# power.net
KiCad netlist of a schematic drawn in Altium Designer
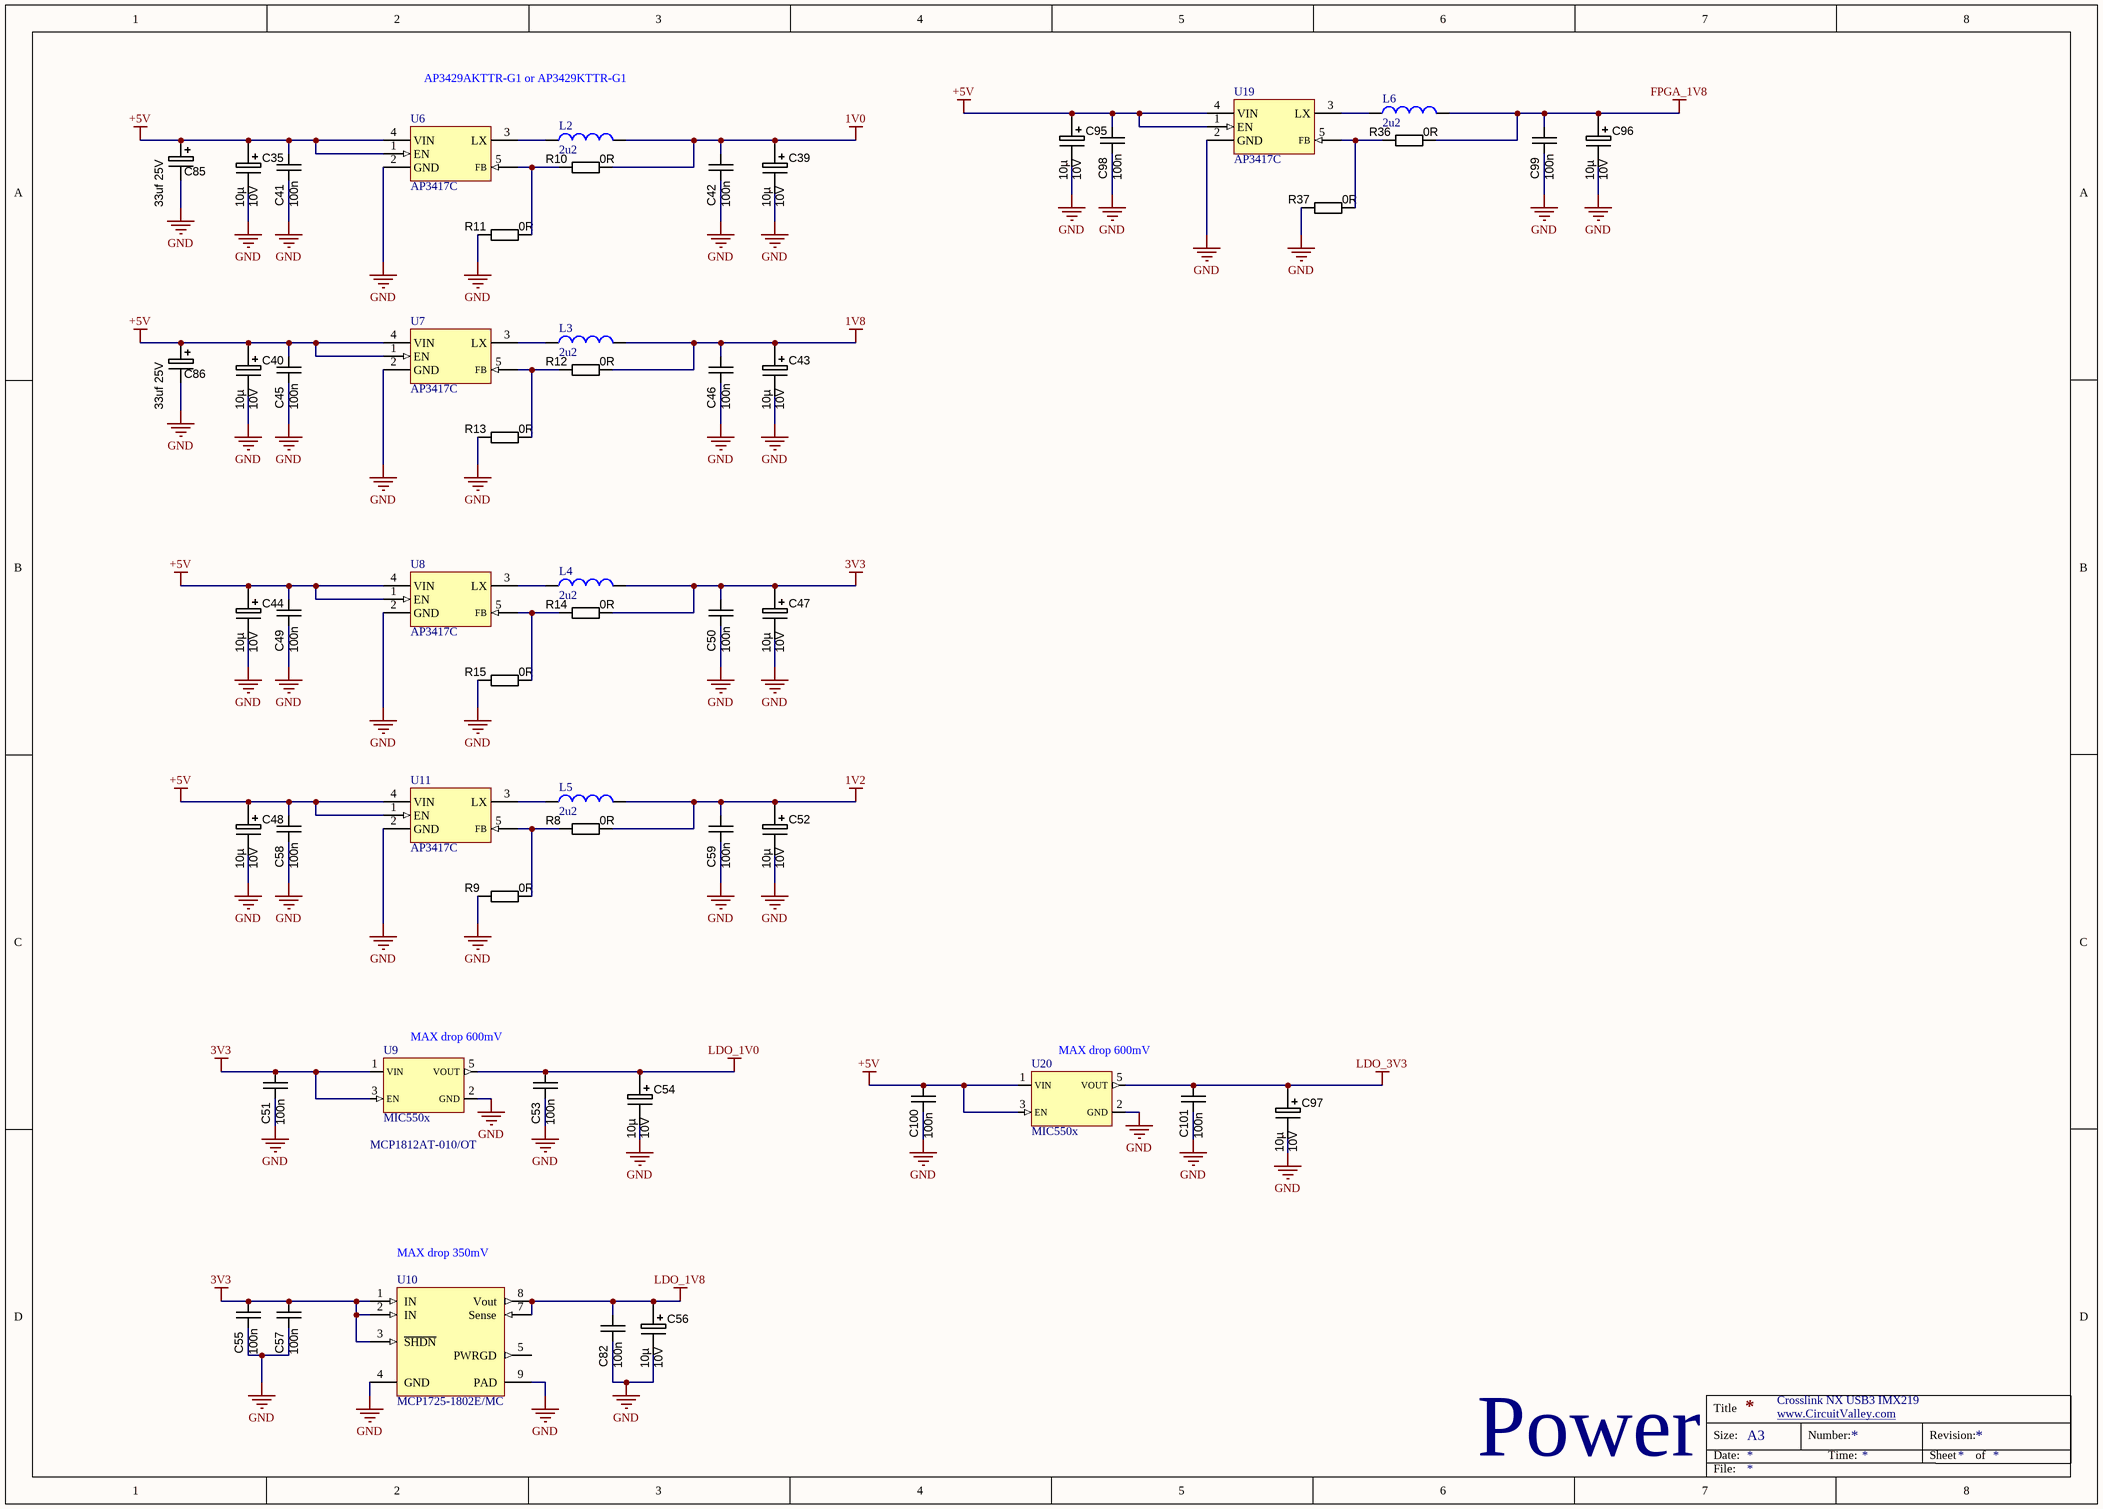
[diagram p0: power.SchDoc]

(export (version "E")
  (design (tool "Eeschema 10.0.6"))
  (components
    (comp (ref "C35")
      (value "10µ")
      (footprint "CAPMP3528X210N")
      (description "Capacitor SMD Tantalum 47uF 20% 6.3V 1210")
      (fields (field (name "TOLERANCE") "±20%") (field (name "RATINGS") "10V"))
      (libsource (lib "PBL - Capacitors") (part "CAPT_47u_1210_6V3"))
    )
    (comp (ref "C39")
      (value "10µ")
      (footprint "CAPMP3528X210N")
      (description "Capacitor SMD Tantalum 47uF 20% 6.3V 1210")
      (fields (field (name "TOLERANCE") "±20%") (field (name "RATINGS") "10V"))
      (libsource (lib "PBL - Capacitors") (part "CAPT_47u_1210_6V3"))
    )
    (comp (ref "C40")
      (value "10µ")
      (footprint "CAPMP3528X210N")
      (description "Capacitor SMD Tantalum 47uF 20% 6.3V 1210")
      (fields (field (name "TOLERANCE") "±20%") (field (name "RATINGS") "10V"))
      (libsource (lib "PBL - Capacitors") (part "CAPT_47u_1210_6V3"))
    )
    (comp (ref "C41")
      (value "100n")
      (footprint "CAPC1608N")
      (description "Capacitor SMD Cer 10pF 5% 50V NP0 0603")
      (fields (field (name "TOLERANCE") "±5%") (field (name "PART") "C0603X104K5RAC"))
      (libsource (lib "PBL - Capacitors") (part "CAPC_10p_0603_NP0_1%_50V"))
    )
    (comp (ref "C42")
      (value "100n")
      (footprint "CAPC1608N")
      (description "Capacitor SMD Cer 10pF 5% 50V NP0 0603")
      (fields (field (name "TOLERANCE") "±5%") (field (name "PART") "C0603X104K5RAC"))
      (libsource (lib "PBL - Capacitors") (part "CAPC_10p_0603_NP0_1%_50V"))
    )
    (comp (ref "C43")
      (value "10µ")
      (footprint "CAPMP3528X210N")
      (description "Capacitor SMD Tantalum 47uF 20% 6.3V 1210")
      (fields (field (name "TOLERANCE") "±20%") (field (name "RATINGS") "10V"))
      (libsource (lib "PBL - Capacitors") (part "CAPT_47u_1210_6V3"))
    )
    (comp (ref "C44")
      (value "10µ")
      (footprint "CAPMP3528X210N")
      (description "Capacitor SMD Tantalum 47uF 20% 6.3V 1210")
      (fields (field (name "TOLERANCE") "±20%") (field (name "RATINGS") "10V"))
      (libsource (lib "PBL - Capacitors") (part "CAPT_47u_1210_6V3"))
    )
    (comp (ref "C45")
      (value "100n")
      (footprint "CAPC1608N")
      (description "Capacitor SMD Cer 10pF 5% 50V NP0 0603")
      (fields (field (name "TOLERANCE") "±5%") (field (name "PART") "C0603X104K5RAC"))
      (libsource (lib "PBL - Capacitors") (part "CAPC_10p_0603_NP0_1%_50V"))
    )
    (comp (ref "C46")
      (value "100n")
      (footprint "CAPC1608N")
      (description "Capacitor SMD Cer 10pF 5% 50V NP0 0603")
      (fields (field (name "TOLERANCE") "±5%") (field (name "PART") "C0603X104K5RAC"))
      (libsource (lib "PBL - Capacitors") (part "CAPC_10p_0603_NP0_1%_50V"))
    )
    (comp (ref "C47")
      (value "10µ")
      (footprint "CAPMP3528X210N")
      (description "Capacitor SMD Tantalum 47uF 20% 6.3V 1210")
      (fields (field (name "TOLERANCE") "±20%") (field (name "RATINGS") "10V"))
      (libsource (lib "PBL - Capacitors") (part "CAPT_47u_1210_6V3"))
    )
    (comp (ref "C48")
      (value "10µ")
      (footprint "CAPMP3528X210N")
      (description "Capacitor SMD Tantalum 47uF 20% 6.3V 1210")
      (fields (field (name "TOLERANCE") "±20%") (field (name "RATINGS") "10V"))
      (libsource (lib "PBL - Capacitors") (part "CAPT_47u_1210_6V3"))
    )
    (comp (ref "C49")
      (value "100n")
      (footprint "CAPC1608N")
      (description "Capacitor SMD Cer 10pF 5% 50V NP0 0603")
      (fields (field (name "TOLERANCE") "±5%") (field (name "PART") "C0603X104K5RAC"))
      (libsource (lib "PBL - Capacitors") (part "CAPC_10p_0603_NP0_1%_50V"))
    )
    (comp (ref "C50")
      (value "100n")
      (footprint "CAPC1608N")
      (description "Capacitor SMD Cer 10pF 5% 50V NP0 0603")
      (fields (field (name "TOLERANCE") "±5%") (field (name "PART") "C0603X104K5RAC"))
      (libsource (lib "PBL - Capacitors") (part "CAPC_10p_0603_NP0_1%_50V"))
    )
    (comp (ref "C51")
      (value "100n")
      (footprint "CAPC1608N")
      (description "Capacitor SMD Cer 10pF 5% 50V NP0 0603")
      (fields (field (name "TOLERANCE") "±5%") (field (name "PART") "C0603X104K5RAC"))
      (libsource (lib "PBL - Capacitors") (part "CAPC_10p_0603_NP0_1%_50V"))
    )
    (comp (ref "C52")
      (value "10µ")
      (footprint "CAPMP3528X210N")
      (description "Capacitor SMD Tantalum 47uF 20% 6.3V 1210")
      (fields (field (name "TOLERANCE") "±20%") (field (name "RATINGS") "10V"))
      (libsource (lib "PBL - Capacitors") (part "CAPT_47u_1210_6V3"))
    )
    (comp (ref "C53")
      (value "100n")
      (footprint "CAPC1608N")
      (description "Capacitor SMD Cer 10pF 5% 50V NP0 0603")
      (fields (field (name "TOLERANCE") "±5%") (field (name "PART") "C0603X104K5RAC"))
      (libsource (lib "PBL - Capacitors") (part "CAPC_10p_0603_NP0_1%_50V"))
    )
    (comp (ref "C54")
      (value "10µ")
      (footprint "CAPMP3528X210N")
      (description "Capacitor SMD Tantalum 47uF 20% 6.3V 1210")
      (fields (field (name "TOLERANCE") "±20%") (field (name "RATINGS") "10V"))
      (libsource (lib "PBL - Capacitors") (part "CAPT_47u_1210_6V3"))
    )
    (comp (ref "C55")
      (value "100n")
      (footprint "CAPC1608N")
      (description "Capacitor SMD Cer 10pF 5% 50V NP0 0603")
      (fields (field (name "TOLERANCE") "±5%") (field (name "PART") "C0603X104K5RAC"))
      (libsource (lib "PBL - Capacitors") (part "CAPC_10p_0603_NP0_1%_50V"))
    )
    (comp (ref "C56")
      (value "10µ")
      (footprint "CAPMP3528X210N")
      (description "Capacitor SMD Tantalum 47uF 20% 6.3V 1210")
      (fields (field (name "TOLERANCE") "±20%") (field (name "RATINGS") "10V"))
      (libsource (lib "PBL - Capacitors") (part "CAPT_47u_1210_6V3"))
    )
    (comp (ref "C57")
      (value "100n")
      (footprint "CAPC1608N")
      (description "Capacitor SMD Cer 10pF 5% 50V NP0 0603")
      (fields (field (name "TOLERANCE") "±5%") (field (name "PART") "C0603X104K5RAC"))
      (libsource (lib "PBL - Capacitors") (part "CAPC_10p_0603_NP0_1%_50V"))
    )
    (comp (ref "C58")
      (value "100n")
      (footprint "CAPC1608N")
      (description "Capacitor SMD Cer 10pF 5% 50V NP0 0603")
      (fields (field (name "TOLERANCE") "±5%") (field (name "PART") "C0603X104K5RAC"))
      (libsource (lib "PBL - Capacitors") (part "CAPC_10p_0603_NP0_1%_50V"))
    )
    (comp (ref "C59")
      (value "100n")
      (footprint "CAPC1608N")
      (description "Capacitor SMD Cer 10pF 5% 50V NP0 0603")
      (fields (field (name "TOLERANCE") "±5%") (field (name "PART") "C0603X104K5RAC"))
      (libsource (lib "PBL - Capacitors") (part "CAPC_10p_0603_NP0_1%_50V"))
    )
    (comp (ref "C82")
      (value "100n")
      (footprint "CAPC1608N")
      (description "Capacitor SMD Cer 10pF 5% 50V NP0 0603")
      (fields (field (name "TOLERANCE") "±5%") (field (name "PART") "C0603X104K5RAC"))
      (libsource (lib "PBL - Capacitors") (part "CAPC_10p_0603_NP0_1%_50V"))
    )
    (comp (ref "C85")
      (value "33uf 25V")
      (footprint "CAPMP7343X310N")
      (description "Capacitor SMD Tant 330uF 20% 6V3 2917")
      (fields
        (field (name "TOLERANCE") "±20%")
        (field (name "MANUFACTURER PART NUMBER") "T520D337M006ATE015")
      )
      (libsource (lib "PBL - Capacitors") (part "CAPT_330u_2917_6V3"))
    )
    (comp (ref "C86")
      (value "33uf 25V")
      (footprint "CAPMP7343X310N")
      (description "Capacitor SMD Tant 330uF 20% 6V3 2917")
      (fields
        (field (name "TOLERANCE") "±20%")
        (field (name "MANUFACTURER PART NUMBER") "T520D337M006ATE015")
      )
      (libsource (lib "PBL - Capacitors") (part "CAPT_330u_2917_6V3"))
    )
    (comp (ref "C95")
      (value "10µ")
      (footprint "CAPMP3528X210N")
      (description "Capacitor SMD Tantalum 47uF 20% 6.3V 1210")
      (fields (field (name "TOLERANCE") "±20%") (field (name "RATINGS") "10V"))
      (libsource (lib "PBL - Capacitors") (part "CAPT_47u_1210_6V3"))
    )
    (comp (ref "C96")
      (value "10µ")
      (footprint "CAPMP3528X210N")
      (description "Capacitor SMD Tantalum 47uF 20% 6.3V 1210")
      (fields (field (name "TOLERANCE") "±20%") (field (name "RATINGS") "10V"))
      (libsource (lib "PBL - Capacitors") (part "CAPT_47u_1210_6V3"))
    )
    (comp (ref "C97")
      (value "10µ")
      (footprint "CAPMP3528X210N")
      (description "Capacitor SMD Tantalum 47uF 20% 6.3V 1210")
      (fields (field (name "TOLERANCE") "±20%") (field (name "RATINGS") "10V"))
      (libsource (lib "PBL - Capacitors") (part "CAPT_47u_1210_6V3"))
    )
    (comp (ref "C98")
      (value "100n")
      (footprint "CAPC1608N")
      (description "Capacitor SMD Cer 10pF 5% 50V NP0 0603")
      (fields (field (name "TOLERANCE") "±5%") (field (name "PART") "C0603X104K5RAC"))
      (libsource (lib "PBL - Capacitors") (part "CAPC_10p_0603_NP0_1%_50V"))
    )
    (comp (ref "C99")
      (value "100n")
      (footprint "CAPC1608N")
      (description "Capacitor SMD Cer 10pF 5% 50V NP0 0603")
      (fields (field (name "TOLERANCE") "±5%") (field (name "PART") "C0603X104K5RAC"))
      (libsource (lib "PBL - Capacitors") (part "CAPC_10p_0603_NP0_1%_50V"))
    )
    (comp (ref "C100")
      (value "100n")
      (footprint "CAPC1608N")
      (description "Capacitor SMD Cer 10pF 5% 50V NP0 0603")
      (fields (field (name "TOLERANCE") "±5%") (field (name "PART") "C0603X104K5RAC"))
      (libsource (lib "PBL - Capacitors") (part "CAPC_10p_0603_NP0_1%_50V"))
    )
    (comp (ref "C101")
      (value "100n")
      (footprint "CAPC1608N")
      (description "Capacitor SMD Cer 10pF 5% 50V NP0 0603")
      (fields (field (name "TOLERANCE") "±5%") (field (name "PART") "C0603X104K5RAC"))
      (libsource (lib "PBL - Capacitors") (part "CAPC_10p_0603_NP0_1%_50V"))
    )
    (comp (ref "L2")
      (value "2u2")
      (footprint "TAIYO_NRS4018T2R2MDGJ")
      (fields (field (name "PARTNUMBER") "NRS4018T2R2MDGJ"))
      (libsource (lib "Inductor") (part "inductor_smd"))
    )
    (comp (ref "L3")
      (value "2u2")
      (footprint "TAIYO_NRS4018T2R2MDGJ")
      (fields (field (name "PARTNUMBER") "NRS4018T2R2MDGJ"))
      (libsource (lib "Inductor") (part "inductor_smd"))
    )
    (comp (ref "L4")
      (value "2u2")
      (footprint "TAIYO_NRS4018T2R2MDGJ")
      (fields (field (name "PARTNUMBER") "NRS4018T2R2MDGJ"))
      (libsource (lib "Inductor") (part "inductor_smd"))
    )
    (comp (ref "L5")
      (value "2u2")
      (footprint "TAIYO_NRS4018T2R2MDGJ")
      (fields (field (name "PARTNUMBER") "NRS4018T2R2MDGJ"))
      (libsource (lib "Inductor") (part "inductor_smd"))
    )
    (comp (ref "L6")
      (value "2u2")
      (footprint "TAIYO_NRS4018T2R2MDGJ")
      (fields (field (name "PARTNUMBER") "NRS4018T2R2MDGJ"))
      (libsource (lib "Inductor") (part "inductor_smd"))
    )
    (comp (ref "R8")
      (value "0R")
      (footprint "RESC1608N_ZERO")
      (description "Resistor SMD chip 0.0 Ohm 0.1W 0603")
      (fields (field (name "TOLERANCE") "±5%") (field (name "Comment") "Thick Film"))
      (libsource (lib "PBL - Resistors") (part "RES_0R_0603"))
    )
    (comp (ref "R9")
      (value "0R")
      (footprint "RESC1608N_ZERO")
      (description "Resistor SMD chip 0.0 Ohm 0.1W 0603")
      (fields (field (name "TOLERANCE") "±5%") (field (name "Comment") "Thick Film"))
      (libsource (lib "PBL - Resistors") (part "RES_0R_0603"))
    )
    (comp (ref "R10")
      (value "0R")
      (footprint "RESC1608N_ZERO")
      (description "Resistor SMD chip 0.0 Ohm 0.1W 0603")
      (fields (field (name "TOLERANCE") "±5%") (field (name "Comment") "Thick Film"))
      (libsource (lib "PBL - Resistors") (part "RES_0R_0603"))
    )
    (comp (ref "R11")
      (value "0R")
      (footprint "RESC1608N_ZERO")
      (description "Resistor SMD chip 0.0 Ohm 0.1W 0603")
      (fields (field (name "TOLERANCE") "±5%") (field (name "Comment") "Thick Film"))
      (libsource (lib "PBL - Resistors") (part "RES_0R_0603"))
    )
    (comp (ref "R12")
      (value "0R")
      (footprint "RESC1608N_ZERO")
      (description "Resistor SMD chip 0.0 Ohm 0.1W 0603")
      (fields (field (name "TOLERANCE") "±5%") (field (name "Comment") "Thick Film"))
      (libsource (lib "PBL - Resistors") (part "RES_0R_0603"))
    )
    (comp (ref "R13")
      (value "0R")
      (footprint "RESC1608N_ZERO")
      (description "Resistor SMD chip 0.0 Ohm 0.1W 0603")
      (fields (field (name "TOLERANCE") "±5%") (field (name "Comment") "Thick Film"))
      (libsource (lib "PBL - Resistors") (part "RES_0R_0603"))
    )
    (comp (ref "R14")
      (value "0R")
      (footprint "RESC1608N_ZERO")
      (description "Resistor SMD chip 0.0 Ohm 0.1W 0603")
      (fields (field (name "TOLERANCE") "±5%") (field (name "Comment") "Thick Film"))
      (libsource (lib "PBL - Resistors") (part "RES_0R_0603"))
    )
    (comp (ref "R15")
      (value "0R")
      (footprint "RESC1608N_ZERO")
      (description "Resistor SMD chip 0.0 Ohm 0.1W 0603")
      (fields (field (name "TOLERANCE") "±5%") (field (name "Comment") "Thick Film"))
      (libsource (lib "PBL - Resistors") (part "RES_0R_0603"))
    )
    (comp (ref "R36")
      (value "0R")
      (footprint "RESC1608N_ZERO")
      (description "Resistor SMD chip 0.0 Ohm 0.1W 0603")
      (fields (field (name "TOLERANCE") "±5%") (field (name "Comment") "Thick Film"))
      (libsource (lib "PBL - Resistors") (part "RES_0R_0603"))
    )
    (comp (ref "R37")
      (value "0R")
      (footprint "RESC1608N_ZERO")
      (description "Resistor SMD chip 0.0 Ohm 0.1W 0603")
      (fields (field (name "TOLERANCE") "±5%") (field (name "Comment") "Thick Film"))
      (libsource (lib "PBL - Resistors") (part "RES_0R_0603"))
    )
    (comp (ref "U6") (value "AP3417C") (footprint "SOT23-5") (libsource (lib "cvlib") (part "AP3417C")))
    (comp (ref "U7") (value "AP3417C") (footprint "SOT23-5") (libsource (lib "cvlib") (part "AP3417C")))
    (comp (ref "U8") (value "AP3417C") (footprint "SOT23-5") (libsource (lib "cvlib") (part "AP3417C")))
    (comp (ref "U9") (value "MIC550x") (footprint "SOT23-5") (libsource (lib "cvlib") (part "MIC550x")))
    (comp (ref "U10")
      (value "MCP1725-1802E/MC")
      (footprint "DFN8_3x2")
      (description "LDO")
      (libsource (lib "cvlib") (part "MCP1725"))
    )
    (comp (ref "U11") (value "AP3417C") (footprint "SOT23-5") (libsource (lib "cvlib") (part "AP3417C")))
    (comp (ref "U19") (value "AP3417C") (footprint "SOT23-5") (libsource (lib "cvlib") (part "AP3417C")))
    (comp (ref "U20") (value "MIC550x") (footprint "SOT23-5") (libsource (lib "cvlib") (part "MIC550x")))
  )
  (nets
    (net (code "1") (name "+5V") (class "Default")
      (node (ref "C100") (pin "2") (pintype "passive"))
      (node (ref "C35") (pin "1") (pintype "passive"))
      (node (ref "C40") (pin "1") (pintype "passive"))
      (node (ref "C41") (pin "2") (pintype "passive"))
      (node (ref "C44") (pin "1") (pintype "passive"))
      (node (ref "C45") (pin "2") (pintype "passive"))
      (node (ref "C48") (pin "1") (pintype "passive"))
      (node (ref "C49") (pin "2") (pintype "passive"))
      (node (ref "C58") (pin "2") (pintype "passive"))
      (node (ref "C85") (pin "1") (pintype "passive"))
      (node (ref "C86") (pin "1") (pintype "passive"))
      (node (ref "C95") (pin "1") (pintype "passive"))
      (node (ref "C98") (pin "2") (pintype "passive"))
      (node (ref "U11") (pin "1") (pinfunction "EN_1") (pintype "input"))
      (node (ref "U11") (pin "4") (pinfunction "VIN_4") (pintype "power_in"))
      (node (ref "U19") (pin "1") (pinfunction "EN_1") (pintype "input"))
      (node (ref "U19") (pin "4") (pinfunction "VIN_4") (pintype "power_in"))
      (node (ref "U20") (pin "1") (pinfunction "VIN_1") (pintype "power_in"))
      (node (ref "U20") (pin "3") (pinfunction "EN_3") (pintype "input"))
      (node (ref "U6") (pin "1") (pinfunction "EN_1") (pintype "input"))
      (node (ref "U6") (pin "4") (pinfunction "VIN_4") (pintype "power_in"))
      (node (ref "U7") (pin "1") (pinfunction "EN_1") (pintype "input"))
      (node (ref "U7") (pin "4") (pinfunction "VIN_4") (pintype "power_in"))
      (node (ref "U8") (pin "1") (pinfunction "EN_1") (pintype "input"))
      (node (ref "U8") (pin "4") (pinfunction "VIN_4") (pintype "power_in"))
    )
    (net (code "2") (name "1V0") (class "Default")
      (node (ref "C39") (pin "1") (pintype "passive"))
      (node (ref "C42") (pin "2") (pintype "passive"))
      (node (ref "L2") (pin "2") (pinfunction "2_2") (pintype "passive"))
      (node (ref "R10") (pin "1") (pinfunction "1_1") (pintype "passive"))
    )
    (net (code "3") (name "1V2") (class "Default")
      (node (ref "C52") (pin "1") (pintype "passive"))
      (node (ref "C59") (pin "2") (pintype "passive"))
      (node (ref "L5") (pin "2") (pinfunction "2_2") (pintype "passive"))
      (node (ref "R8") (pin "1") (pinfunction "1_1") (pintype "passive"))
    )
    (net (code "4") (name "1V8") (class "Default")
      (node (ref "C43") (pin "1") (pintype "passive"))
      (node (ref "C46") (pin "2") (pintype "passive"))
      (node (ref "L3") (pin "2") (pinfunction "2_2") (pintype "passive"))
      (node (ref "R12") (pin "1") (pinfunction "1_1") (pintype "passive"))
    )
    (net (code "5") (name "3V3") (class "Default")
      (node (ref "C47") (pin "1") (pintype "passive"))
      (node (ref "C50") (pin "2") (pintype "passive"))
      (node (ref "C51") (pin "2") (pintype "passive"))
      (node (ref "C55") (pin "2") (pintype "passive"))
      (node (ref "C57") (pin "2") (pintype "passive"))
      (node (ref "L4") (pin "2") (pinfunction "2_2") (pintype "passive"))
      (node (ref "R14") (pin "1") (pinfunction "1_1") (pintype "passive"))
      (node (ref "U10") (pin "1") (pinfunction "IN_1") (pintype "input"))
      (node (ref "U10") (pin "2") (pinfunction "IN_2") (pintype "input"))
      (node (ref "U10") (pin "3") (pinfunction "~{SHDN}_3") (pintype "input"))
      (node (ref "U9") (pin "1") (pinfunction "VIN_1") (pintype "power_in"))
      (node (ref "U9") (pin "3") (pinfunction "EN_3") (pintype "input"))
    )
    (net (code "6") (name "FPGA_1V8") (class "Default")
      (node (ref "C96") (pin "1") (pintype "passive"))
      (node (ref "C99") (pin "2") (pintype "passive"))
      (node (ref "L6") (pin "2") (pinfunction "2_2") (pintype "passive"))
      (node (ref "R36") (pin "1") (pinfunction "1_1") (pintype "passive"))
    )
    (net (code "7") (name "GND") (class "Default")
      (node (ref "C100") (pin "1") (pintype "passive"))
      (node (ref "C101") (pin "1") (pintype "passive"))
      (node (ref "C35") (pin "2") (pintype "passive"))
      (node (ref "C39") (pin "2") (pintype "passive"))
      (node (ref "C40") (pin "2") (pintype "passive"))
      (node (ref "C41") (pin "1") (pintype "passive"))
      (node (ref "C42") (pin "1") (pintype "passive"))
      (node (ref "C43") (pin "2") (pintype "passive"))
      (node (ref "C44") (pin "2") (pintype "passive"))
      (node (ref "C45") (pin "1") (pintype "passive"))
      (node (ref "C46") (pin "1") (pintype "passive"))
      (node (ref "C47") (pin "2") (pintype "passive"))
      (node (ref "C48") (pin "2") (pintype "passive"))
      (node (ref "C49") (pin "1") (pintype "passive"))
      (node (ref "C50") (pin "1") (pintype "passive"))
      (node (ref "C51") (pin "1") (pintype "passive"))
      (node (ref "C52") (pin "2") (pintype "passive"))
      (node (ref "C53") (pin "1") (pintype "passive"))
      (node (ref "C54") (pin "2") (pintype "passive"))
      (node (ref "C55") (pin "1") (pintype "passive"))
      (node (ref "C56") (pin "2") (pintype "passive"))
      (node (ref "C57") (pin "1") (pintype "passive"))
      (node (ref "C58") (pin "1") (pintype "passive"))
      (node (ref "C59") (pin "1") (pintype "passive"))
      (node (ref "C82") (pin "1") (pintype "passive"))
      (node (ref "C85") (pin "2") (pintype "passive"))
      (node (ref "C86") (pin "2") (pintype "passive"))
      (node (ref "C95") (pin "2") (pintype "passive"))
      (node (ref "C96") (pin "2") (pintype "passive"))
      (node (ref "C97") (pin "2") (pintype "passive"))
      (node (ref "C98") (pin "1") (pintype "passive"))
      (node (ref "C99") (pin "1") (pintype "passive"))
      (node (ref "R11") (pin "2") (pinfunction "2_2") (pintype "passive"))
      (node (ref "R13") (pin "2") (pinfunction "2_2") (pintype "passive"))
      (node (ref "R15") (pin "2") (pinfunction "2_2") (pintype "passive"))
      (node (ref "R37") (pin "2") (pinfunction "2_2") (pintype "passive"))
      (node (ref "R9") (pin "2") (pinfunction "2_2") (pintype "passive"))
      (node (ref "U10") (pin "4") (pinfunction "GND_4") (pintype "passive"))
      (node (ref "U10") (pin "9") (pinfunction "PAD_9") (pintype "passive"))
      (node (ref "U11") (pin "2") (pinfunction "GND_2") (pintype "power_in"))
      (node (ref "U19") (pin "2") (pinfunction "GND_2") (pintype "power_in"))
      (node (ref "U20") (pin "2") (pinfunction "GND_2") (pintype "power_in"))
      (node (ref "U6") (pin "2") (pinfunction "GND_2") (pintype "power_in"))
      (node (ref "U7") (pin "2") (pinfunction "GND_2") (pintype "power_in"))
      (node (ref "U8") (pin "2") (pinfunction "GND_2") (pintype "power_in"))
      (node (ref "U9") (pin "2") (pinfunction "GND_2") (pintype "power_in"))
    )
    (net (code "8") (name "LDO_1V0") (class "Default")
      (node (ref "C53") (pin "2") (pintype "passive"))
      (node (ref "C54") (pin "1") (pintype "passive"))
      (node (ref "U9") (pin "5") (pinfunction "VOUT_5") (pintype "output"))
    )
    (net (code "9") (name "LDO_1V8") (class "Default")
      (node (ref "C56") (pin "1") (pintype "passive"))
      (node (ref "C82") (pin "2") (pintype "passive"))
      (node (ref "U10") (pin "7") (pinfunction "Sense_7") (pintype "input"))
      (node (ref "U10") (pin "8") (pinfunction "Vout_8") (pintype "output"))
    )
    (net (code "10") (name "LDO_3V3") (class "Default")
      (node (ref "C101") (pin "2") (pintype "passive"))
      (node (ref "C97") (pin "1") (pintype "passive"))
      (node (ref "U20") (pin "5") (pinfunction "VOUT_5") (pintype "output"))
    )
    (net (code "11") (name "Net-(U6-FB)") (class "Default")
      (node (ref "R10") (pin "2") (pinfunction "2_2") (pintype "passive"))
      (node (ref "R11") (pin "1") (pinfunction "1_1") (pintype "passive"))
      (node (ref "U6") (pin "5") (pinfunction "FB_5") (pintype "input"))
    )
    (net (code "12") (name "Net-(U6-LX)") (class "Default")
      (node (ref "L2") (pin "1") (pinfunction "1_1") (pintype "passive"))
      (node (ref "U6") (pin "3") (pinfunction "LX_3") (pintype "passive"))
    )
    (net (code "13") (name "Net-(U7-FB)") (class "Default")
      (node (ref "R12") (pin "2") (pinfunction "2_2") (pintype "passive"))
      (node (ref "R13") (pin "1") (pinfunction "1_1") (pintype "passive"))
      (node (ref "U7") (pin "5") (pinfunction "FB_5") (pintype "input"))
    )
    (net (code "14") (name "Net-(U7-LX)") (class "Default")
      (node (ref "L3") (pin "1") (pinfunction "1_1") (pintype "passive"))
      (node (ref "U7") (pin "3") (pinfunction "LX_3") (pintype "passive"))
    )
    (net (code "15") (name "Net-(U8-FB)") (class "Default")
      (node (ref "R14") (pin "2") (pinfunction "2_2") (pintype "passive"))
      (node (ref "R15") (pin "1") (pinfunction "1_1") (pintype "passive"))
      (node (ref "U8") (pin "5") (pinfunction "FB_5") (pintype "input"))
    )
    (net (code "16") (name "Net-(U8-LX)") (class "Default")
      (node (ref "L4") (pin "1") (pinfunction "1_1") (pintype "passive"))
      (node (ref "U8") (pin "3") (pinfunction "LX_3") (pintype "passive"))
    )
    (net (code "17") (name "Net-(U11-FB)") (class "Default")
      (node (ref "R8") (pin "2") (pinfunction "2_2") (pintype "passive"))
      (node (ref "R9") (pin "1") (pinfunction "1_1") (pintype "passive"))
      (node (ref "U11") (pin "5") (pinfunction "FB_5") (pintype "input"))
    )
    (net (code "18") (name "Net-(U11-LX)") (class "Default")
      (node (ref "L5") (pin "1") (pinfunction "1_1") (pintype "passive"))
      (node (ref "U11") (pin "3") (pinfunction "LX_3") (pintype "passive"))
    )
    (net (code "19") (name "Net-(U19-FB)") (class "Default")
      (node (ref "R36") (pin "2") (pinfunction "2_2") (pintype "passive"))
      (node (ref "R37") (pin "1") (pinfunction "1_1") (pintype "passive"))
      (node (ref "U19") (pin "5") (pinfunction "FB_5") (pintype "input"))
    )
    (net (code "20") (name "Net-(U19-LX)") (class "Default")
      (node (ref "L6") (pin "1") (pinfunction "1_1") (pintype "passive"))
      (node (ref "U19") (pin "3") (pinfunction "LX_3") (pintype "passive"))
    )
    (net (code "21") (name "unconnected-(U10-PWRGD-Pad5)") (class "Default")
      (node (ref "U10") (pin "5") (pinfunction "PWRGD_5") (pintype "output"))
    )
  )
)
